# adapter_board.net
KiCad netlist of a schematic drawn in Altium Designer
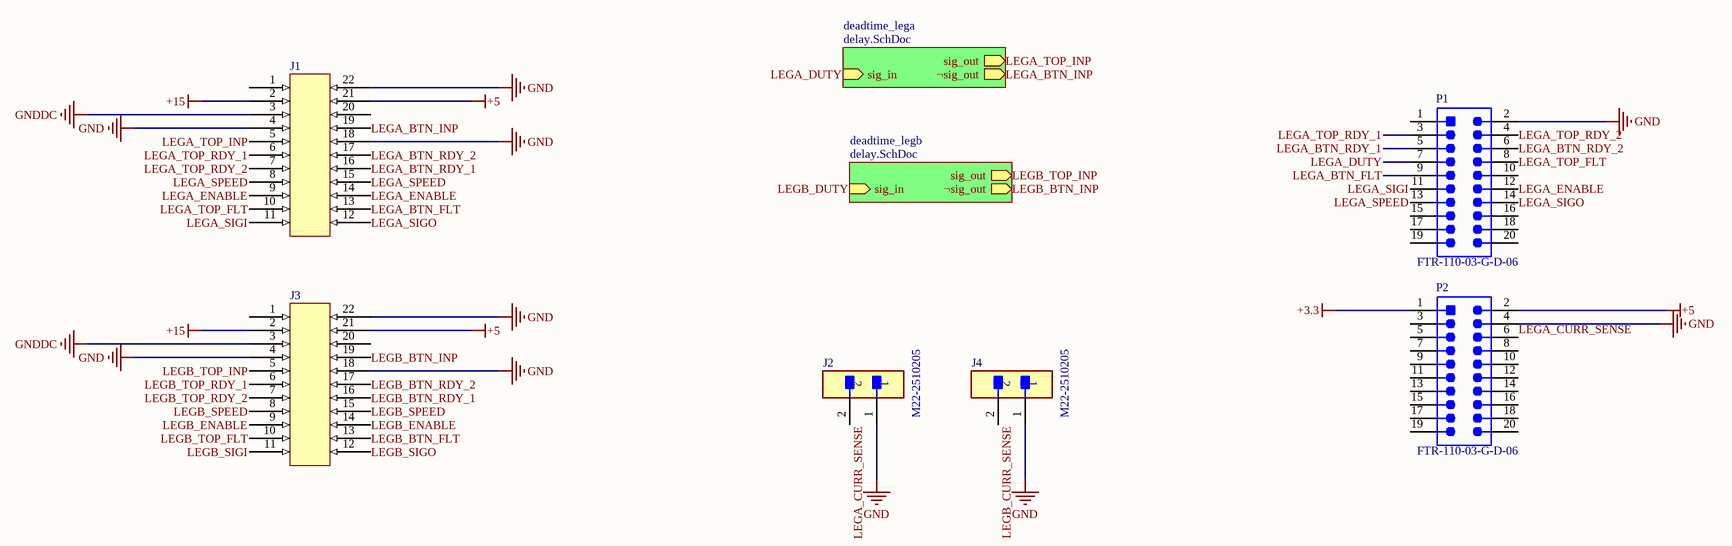
[diagram p0: adapter_board.SchDoc]

(export (version "E")
  (design (tool "Eeschema 10.0.6"))
  (components
    (comp (ref "J1")
      (value "header_22_milligrid")
      (footprint "header_22_milligrid")
      (libsource (lib "coil_driver_lib") (part "header_22_milligrid"))
    )
    (comp (ref "J2")
      (value "M22-2510205")
      (footprint "FP-M22-2510205-MFG")
      (description "CONN HEADER VERT 2POS 2MM")
      (fields
        (field (name "MANUFACTURER") "Harwin")
        (field (name "OCTOPART") "https://octopart.com/m22-2510205-harwin-2538221")
      )
      (libsource (lib "Altium Content Vault") (part "3bc925449376181038e59eaffc5286c"))
    )
    (comp (ref "J3")
      (value "header_22_milligrid")
      (footprint "header_22_milligrid")
      (libsource (lib "coil_driver_lib") (part "header_22_milligrid"))
    )
    (comp (ref "J4")
      (value "M22-2510205")
      (footprint "FP-M22-2510205-MFG")
      (description "CONN HEADER VERT 2POS 2MM")
      (fields
        (field (name "MANUFACTURER") "Harwin")
        (field (name "OCTOPART") "https://octopart.com/m22-2510205-harwin-2538221")
      )
      (libsource (lib "Altium Content Vault") (part "3bc925449376181038e59eaffc5286c"))
    )
    (comp (ref "P1")
      (value "FTR-110-03-G-D-06")
      (footprint "SMTC-FTR-110-03-G-D-06_V")
      (fields (field (name "MANUFACTURER") "Samtec"))
      (libsource (lib "Altium Content Vault") (part "CN-2P-M-R20_V1"))
    )
    (comp (ref "P2")
      (value "FTR-110-03-G-D-06")
      (footprint "SMTC-FTR-110-03-G-D-06_V")
      (fields (field (name "MANUFACTURER") "Samtec"))
      (libsource (lib "Altium Content Vault") (part "CN-2P-M-R20_V1"))
    )
  )
  (nets
    (net (code "1") (name "+3.3") (class "Default")
      (node (ref "P2") (pin "1") (pinfunction "1_1") (pintype "passive"))
    )
    (net (code "2") (name "+5") (class "Default")
      (node (ref "J1") (pin "21") (pintype "input"))
      (node (ref "J3") (pin "21") (pintype "input"))
      (node (ref "P2") (pin "2") (pinfunction "2_2") (pintype "passive"))
    )
    (net (code "3") (name "+15") (class "Default")
      (node (ref "J1") (pin "2") (pintype "input"))
      (node (ref "J3") (pin "2") (pintype "input"))
    )
    (net (code "4") (name "/LEGA_BTN_FLT") (class "Default")
      (node (ref "J1") (pin "13") (pintype "input"))
      (node (ref "P1") (pin "9") (pinfunction "9_9") (pintype "passive"))
    )
    (net (code "5") (name "/LEGA_BTN_INP") (class "Default") (node (ref "J1") (pin "19") (pintype "input")))
    (net (code "6") (name "/LEGA_BTN_RDY_1") (class "Default")
      (node (ref "J1") (pin "16") (pintype "input"))
      (node (ref "P1") (pin "5") (pinfunction "5_5") (pintype "passive"))
    )
    (net (code "7") (name "/LEGA_BTN_RDY_2") (class "Default")
      (node (ref "J1") (pin "17") (pintype "input"))
      (node (ref "P1") (pin "6") (pinfunction "6_6") (pintype "passive"))
    )
    (net (code "8") (name "/LEGA_CURR_SENSE") (class "Default")
      (node (ref "J2") (pin "2") (pinfunction "2_2") (pintype "passive"))
      (node (ref "P2") (pin "6") (pinfunction "6_6") (pintype "passive"))
    )
    (net (code "9") (name "/LEGA_DUTY") (class "Default")
      (node (ref "P1") (pin "7") (pinfunction "7_7") (pintype "passive"))
    )
    (net (code "10") (name "/LEGA_ENABLE") (class "Default")
      (node (ref "J1") (pin "14") (pintype "input"))
      (node (ref "J1") (pin "9") (pintype "input"))
      (node (ref "P1") (pin "12") (pinfunction "12_12") (pintype "passive"))
    )
    (net (code "11") (name "/LEGA_SIGI") (class "Default")
      (node (ref "J1") (pin "11") (pintype "input"))
      (node (ref "P1") (pin "11") (pinfunction "11_11") (pintype "passive"))
    )
    (net (code "12") (name "/LEGA_SIGO") (class "Default")
      (node (ref "J1") (pin "12") (pintype "input"))
      (node (ref "P1") (pin "14") (pinfunction "14_14") (pintype "passive"))
    )
    (net (code "13") (name "/LEGA_SPEED") (class "Default")
      (node (ref "J1") (pin "15") (pintype "input"))
      (node (ref "J1") (pin "8") (pintype "input"))
      (node (ref "P1") (pin "13") (pinfunction "13_13") (pintype "passive"))
    )
    (net (code "14") (name "/LEGA_TOP_FLT") (class "Default")
      (node (ref "J1") (pin "10") (pintype "input"))
      (node (ref "P1") (pin "8") (pinfunction "8_8") (pintype "passive"))
    )
    (net (code "15") (name "/LEGA_TOP_INP") (class "Default") (node (ref "J1") (pin "5") (pintype "input")))
    (net (code "16") (name "/LEGA_TOP_RDY_1") (class "Default")
      (node (ref "J1") (pin "6") (pintype "input"))
      (node (ref "P1") (pin "3") (pinfunction "3_3") (pintype "passive"))
    )
    (net (code "17") (name "/LEGA_TOP_RDY_2") (class "Default")
      (node (ref "J1") (pin "7") (pintype "input"))
      (node (ref "P1") (pin "4") (pinfunction "4_4") (pintype "passive"))
    )
    (net (code "18") (name "/LEGB_BTN_FLT") (class "Default") (node (ref "J3") (pin "13") (pintype "input")))
    (net (code "19") (name "/LEGB_BTN_INP") (class "Default") (node (ref "J3") (pin "19") (pintype "input")))
    (net (code "20") (name "/LEGB_BTN_RDY_1") (class "Default")
      (node (ref "J3") (pin "16") (pintype "input"))
    )
    (net (code "21") (name "/LEGB_BTN_RDY_2") (class "Default")
      (node (ref "J3") (pin "17") (pintype "input"))
    )
    (net (code "22") (name "/LEGB_CURR_SENSE") (class "Default")
      (node (ref "J4") (pin "2") (pinfunction "2_2") (pintype "passive"))
    )
    (net (code "24") (name "/LEGB_ENABLE") (class "Default")
      (node (ref "J3") (pin "14") (pintype "input"))
      (node (ref "J3") (pin "9") (pintype "input"))
    )
    (net (code "25") (name "/LEGB_SIGI") (class "Default") (node (ref "J3") (pin "11") (pintype "input")))
    (net (code "26") (name "/LEGB_SIGO") (class "Default") (node (ref "J3") (pin "12") (pintype "input")))
    (net (code "27") (name "/LEGB_SPEED") (class "Default")
      (node (ref "J3") (pin "15") (pintype "input"))
      (node (ref "J3") (pin "8") (pintype "input"))
    )
    (net (code "28") (name "/LEGB_TOP_FLT") (class "Default") (node (ref "J3") (pin "10") (pintype "input")))
    (net (code "29") (name "/LEGB_TOP_INP") (class "Default") (node (ref "J3") (pin "5") (pintype "input")))
    (net (code "30") (name "/LEGB_TOP_RDY_1") (class "Default") (node (ref "J3") (pin "6") (pintype "input")))
    (net (code "31") (name "/LEGB_TOP_RDY_2") (class "Default") (node (ref "J3") (pin "7") (pintype "input")))
    (net (code "32") (name "GND") (class "Default")
      (node (ref "J1") (pin "18") (pintype "input"))
      (node (ref "J1") (pin "22") (pintype "input"))
      (node (ref "J1") (pin "4") (pintype "input"))
      (node (ref "J2") (pin "1") (pinfunction "1_1") (pintype "passive"))
      (node (ref "J3") (pin "18") (pintype "input"))
      (node (ref "J3") (pin "22") (pintype "input"))
      (node (ref "J3") (pin "4") (pintype "input"))
      (node (ref "J4") (pin "1") (pinfunction "1_1") (pintype "passive"))
      (node (ref "P1") (pin "2") (pinfunction "2_2") (pintype "passive"))
      (node (ref "P2") (pin "4") (pinfunction "4_4") (pintype "passive"))
    )
    (net (code "33") (name "GNDDC") (class "Default")
      (node (ref "J1") (pin "3") (pintype "input"))
      (node (ref "J3") (pin "3") (pintype "input"))
    )
    (net (code "34") (name "unconnected-(J1-Pad1)") (class "Default")
      (node (ref "J1") (pin "1") (pintype "input"))
    )
    (net (code "35") (name "unconnected-(J1-Pad20)") (class "Default")
      (node (ref "J1") (pin "20") (pintype "input"))
    )
    (net (code "36") (name "unconnected-(J3-Pad1)") (class "Default")
      (node (ref "J3") (pin "1") (pintype "input"))
    )
    (net (code "37") (name "unconnected-(J3-Pad20)") (class "Default")
      (node (ref "J3") (pin "20") (pintype "input"))
    )
    (net (code "38") (name "unconnected-(P1-Pad1)") (class "Default")
      (node (ref "P1") (pin "1") (pinfunction "1_1") (pintype "passive"))
    )
    (net (code "39") (name "unconnected-(P1-Pad10)") (class "Default")
      (node (ref "P1") (pin "10") (pinfunction "10_10") (pintype "passive"))
    )
    (net (code "40") (name "unconnected-(P1-Pad15)") (class "Default")
      (node (ref "P1") (pin "15") (pinfunction "15_15") (pintype "passive"))
    )
    (net (code "41") (name "unconnected-(P1-Pad16)") (class "Default")
      (node (ref "P1") (pin "16") (pinfunction "16_16") (pintype "passive"))
    )
    (net (code "42") (name "unconnected-(P1-Pad17)") (class "Default")
      (node (ref "P1") (pin "17") (pinfunction "17_17") (pintype "passive"))
    )
    (net (code "43") (name "unconnected-(P1-Pad18)") (class "Default")
      (node (ref "P1") (pin "18") (pinfunction "18_18") (pintype "passive"))
    )
    (net (code "44") (name "unconnected-(P1-Pad19)") (class "Default")
      (node (ref "P1") (pin "19") (pinfunction "19_19") (pintype "passive"))
    )
    (net (code "45") (name "unconnected-(P1-Pad20)") (class "Default")
      (node (ref "P1") (pin "20") (pinfunction "20_20") (pintype "passive"))
    )
    (net (code "46") (name "unconnected-(P2-Pad3)") (class "Default")
      (node (ref "P2") (pin "3") (pinfunction "3_3") (pintype "passive"))
    )
    (net (code "47") (name "unconnected-(P2-Pad5)") (class "Default")
      (node (ref "P2") (pin "5") (pinfunction "5_5") (pintype "passive"))
    )
    (net (code "48") (name "unconnected-(P2-Pad7)") (class "Default")
      (node (ref "P2") (pin "7") (pinfunction "7_7") (pintype "passive"))
    )
    (net (code "49") (name "unconnected-(P2-Pad8)") (class "Default")
      (node (ref "P2") (pin "8") (pinfunction "8_8") (pintype "passive"))
    )
    (net (code "50") (name "unconnected-(P2-Pad9)") (class "Default")
      (node (ref "P2") (pin "9") (pinfunction "9_9") (pintype "passive"))
    )
    (net (code "51") (name "unconnected-(P2-Pad10)") (class "Default")
      (node (ref "P2") (pin "10") (pinfunction "10_10") (pintype "passive"))
    )
    (net (code "52") (name "unconnected-(P2-Pad11)") (class "Default")
      (node (ref "P2") (pin "11") (pinfunction "11_11") (pintype "passive"))
    )
    (net (code "53") (name "unconnected-(P2-Pad12)") (class "Default")
      (node (ref "P2") (pin "12") (pinfunction "12_12") (pintype "passive"))
    )
    (net (code "54") (name "unconnected-(P2-Pad13)") (class "Default")
      (node (ref "P2") (pin "13") (pinfunction "13_13") (pintype "passive"))
    )
    (net (code "55") (name "unconnected-(P2-Pad14)") (class "Default")
      (node (ref "P2") (pin "14") (pinfunction "14_14") (pintype "passive"))
    )
    (net (code "56") (name "unconnected-(P2-Pad15)") (class "Default")
      (node (ref "P2") (pin "15") (pinfunction "15_15") (pintype "passive"))
    )
    (net (code "57") (name "unconnected-(P2-Pad16)") (class "Default")
      (node (ref "P2") (pin "16") (pinfunction "16_16") (pintype "passive"))
    )
    (net (code "58") (name "unconnected-(P2-Pad17)") (class "Default")
      (node (ref "P2") (pin "17") (pinfunction "17_17") (pintype "passive"))
    )
    (net (code "59") (name "unconnected-(P2-Pad18)") (class "Default")
      (node (ref "P2") (pin "18") (pinfunction "18_18") (pintype "passive"))
    )
    (net (code "60") (name "unconnected-(P2-Pad19)") (class "Default")
      (node (ref "P2") (pin "19") (pinfunction "19_19") (pintype "passive"))
    )
    (net (code "61") (name "unconnected-(P2-Pad20)") (class "Default")
      (node (ref "P2") (pin "20") (pinfunction "20_20") (pintype "passive"))
    )
  )
)
